# CC2640R2F_Bluetooth_Beacon.net
KiCad netlist of a schematic drawn in Altium Designer
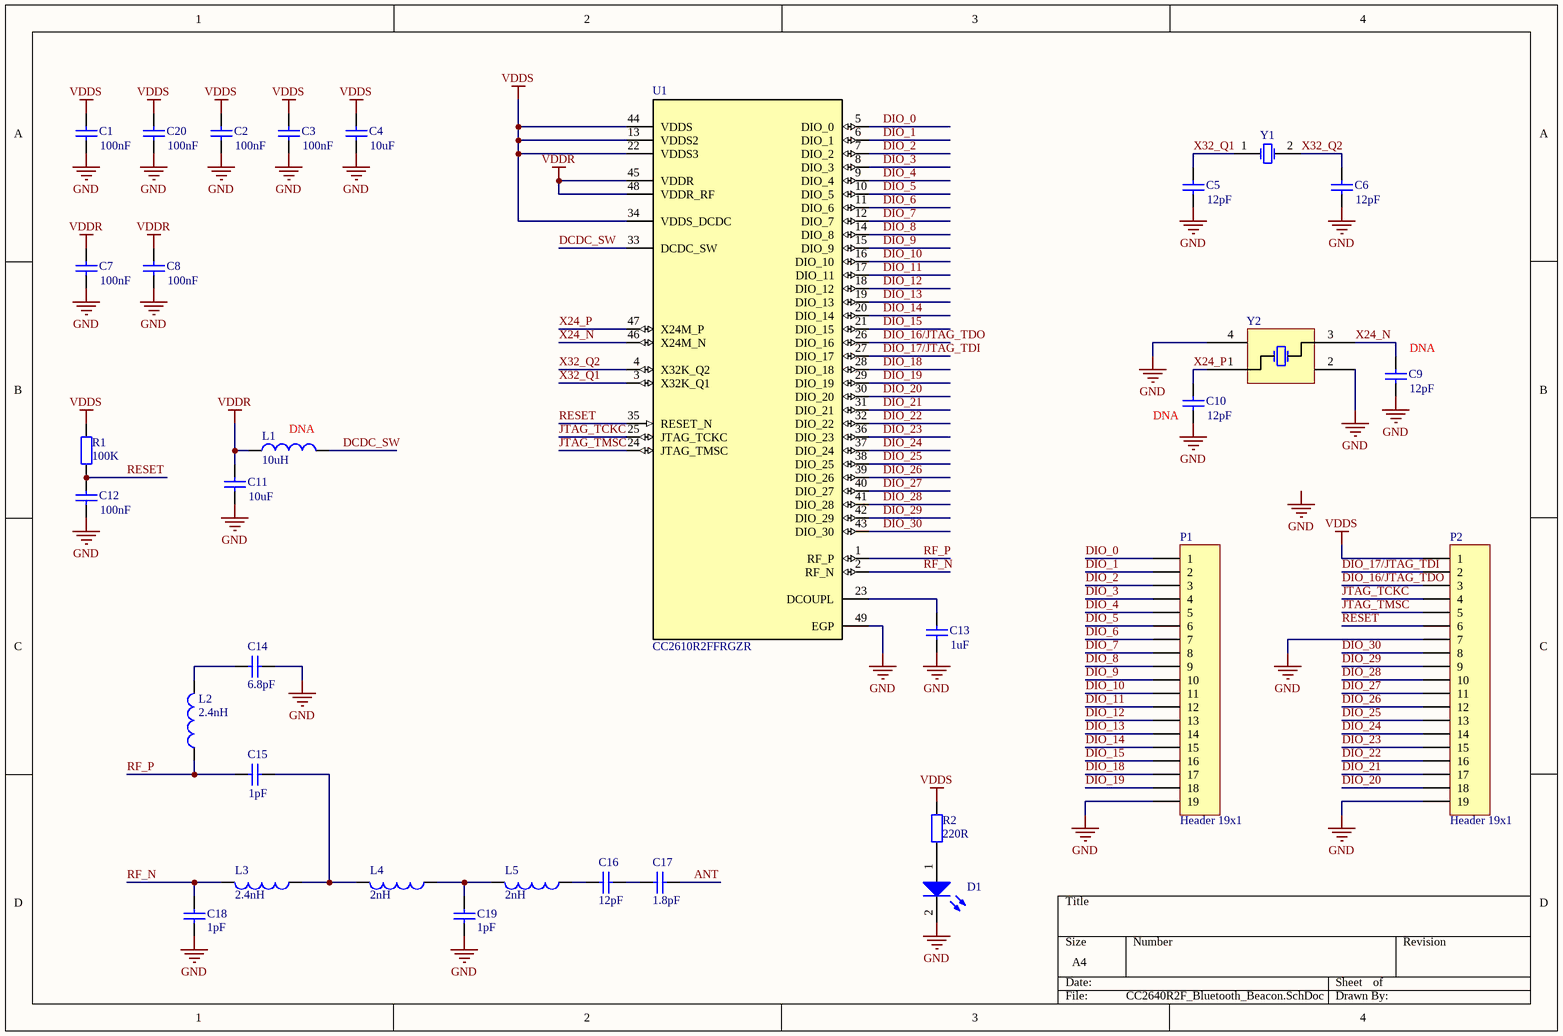
[diagram p0: CC2640R2F_Bluetooth_Beacon.SchDoc]

(export (version "E")
  (design (tool "Eeschema 10.0.6"))
  (components
    (comp (ref "C1")
      (value "100nF")
      (footprint "0603")
      (description "Capacitor")
      (fields (field (name "MPN") "885012206071") (field (name "MANUFACTURER") "Wurth Electronics"))
      (libsource (lib "LibraryTG") (part "Cap"))
    )
    (comp (ref "C2")
      (value "100nF")
      (footprint "0603")
      (description "Capacitor")
      (fields (field (name "MPN") "885012206071") (field (name "MANUFACTURER") "Wurth Electronics"))
      (libsource (lib "LibraryTG") (part "Cap"))
    )
    (comp (ref "C3")
      (value "100nF")
      (footprint "0603")
      (description "Capacitor")
      (fields (field (name "MPN") "885012206071") (field (name "MANUFACTURER") "Wurth Electronics"))
      (libsource (lib "LibraryTG") (part "Cap"))
    )
    (comp (ref "C4")
      (value "10uF")
      (footprint "0603")
      (description "Capacitor")
      (fields (field (name "MPN") "JMK107BJ106MA-T") (field (name "MANUFACTURER") "Taiyo Yuden"))
      (libsource (lib "LibraryTG") (part "Cap"))
    )
    (comp (ref "C5")
      (value "12pF")
      (footprint "0603")
      (description "Capacitor")
      (fields (field (name "MPN") "VJ0603A120KXJPW1BC") (field (name "MANUFACTURER") "Vishay / Vitramon"))
      (libsource (lib "LibraryTG") (part "Cap"))
    )
    (comp (ref "C6")
      (value "12pF")
      (footprint "0603")
      (description "Capacitor")
      (fields (field (name "MPN") "VJ0603A120KXJPW1BC") (field (name "MANUFACTURER") "Vishay / Vitramon"))
      (libsource (lib "LibraryTG") (part "Cap"))
    )
    (comp (ref "C7")
      (value "100nF")
      (footprint "0603")
      (description "Capacitor")
      (fields (field (name "MPN") "885012206071") (field (name "MANUFACTURER") "Wurth Electronics"))
      (libsource (lib "LibraryTG") (part "Cap"))
    )
    (comp (ref "C8")
      (value "100nF")
      (footprint "0603")
      (description "Capacitor")
      (fields (field (name "MPN") "885012206071") (field (name "MANUFACTURER") "Wurth Electronics"))
      (libsource (lib "LibraryTG") (part "Cap"))
    )
    (comp (ref "C9")
      (value "DNA")
      (footprint "0603")
      (description "Capacitor")
      (fields
        (field (name "ALTIUM_VALUE") "12pF")
        (field (name "MPN") "VJ0603A120KXJPW1BC")
        (field (name "MANUFACTURER") "Vishay / Vitramon")
      )
      (libsource (lib "LibraryTG") (part "Cap"))
    )
    (comp (ref "C10")
      (value "DNA")
      (footprint "0603")
      (description "Capacitor")
      (fields
        (field (name "ALTIUM_VALUE") "12pF")
        (field (name "MPN") "VJ0603A120KXJPW1BC")
        (field (name "MANUFACTURER") "Vishay / Vitramon")
      )
      (libsource (lib "LibraryTG") (part "Cap"))
    )
    (comp (ref "C11")
      (value "10uF")
      (footprint "0603")
      (description "Capacitor")
      (fields (field (name "MPN") "JMK107BJ106MA-T") (field (name "MANUFACTURER") "Taiyo Yuden"))
      (libsource (lib "LibraryTG") (part "Cap"))
    )
    (comp (ref "C12")
      (value "100nF")
      (footprint "0603")
      (description "Capacitor")
      (fields (field (name "MPN") "885012206071") (field (name "MANUFACTURER") "Wurth Electronics"))
      (libsource (lib "LibraryTG") (part "Cap"))
    )
    (comp (ref "C13")
      (value "1uF")
      (footprint "0603")
      (description "Capacitor")
      (fields (field (name "MPN") "885012106022") (field (name "MANUFACTURER") "Wurth Electronics"))
      (libsource (lib "LibraryTG") (part "Cap"))
    )
    (comp (ref "C14")
      (value "6.8pF")
      (footprint "0603")
      (description "Capacitor")
      (fields (field (name "MPN") "885012006031") (field (name "MANUFACTURER") "Wurth Electronics"))
      (libsource (lib "LibraryTG") (part "Cap"))
    )
    (comp (ref "C15")
      (value "1pF")
      (footprint "0603")
      (description "Capacitor")
      (fields (field (name "MPN") "885012006087") (field (name "MANUFACTURER") "Wurth Electronics"))
      (libsource (lib "LibraryTG") (part "Cap"))
    )
    (comp (ref "C16")
      (value "12pF")
      (footprint "0603")
      (description "Capacitor")
      (fields (field (name "MPN") "VJ0603A120KXJPW1BC") (field (name "MANUFACTURER") "Vishay / Vitramon"))
      (libsource (lib "LibraryTG") (part "Cap"))
    )
    (comp (ref "C17")
      (value "1.8pF")
      (footprint "0603")
      (description "Capacitor")
      (fields (field (name "MPN") "CC0603CRNPO9BN1R8") (field (name "MANUFACTURER") "Yageo"))
      (libsource (lib "LibraryTG") (part "Cap"))
    )
    (comp (ref "C18")
      (value "1pF")
      (footprint "0603")
      (description "Capacitor")
      (fields (field (name "MPN") "885012006087") (field (name "MANUFACTURER") "Wurth Electronics"))
      (libsource (lib "LibraryTG") (part "Cap"))
    )
    (comp (ref "C19")
      (value "1pF")
      (footprint "0603")
      (description "Capacitor")
      (fields (field (name "MPN") "885012006087") (field (name "MANUFACTURER") "Wurth Electronics"))
      (libsource (lib "LibraryTG") (part "Cap"))
    )
    (comp (ref "C20")
      (value "100nF")
      (footprint "0603")
      (description "Capacitor")
      (fields (field (name "MPN") "885012206071") (field (name "MANUFACTURER") "Wurth Electronics"))
      (libsource (lib "LibraryTG") (part "Cap"))
    )
    (comp (ref "D1")
      (value "LED")
      (footprint "0603")
      (description "Typical RED GaAs LED")
      (fields (field (name "MPN") "150060GS75000") (field (name "MANUFACTURER") "Wurth Electronics"))
      (libsource (lib "LibraryTG") (part "LED"))
    )
    (comp (ref "L1")
      (value "DNA")
      (footprint "0603")
      (description "Inductor")
      (fields (field (name "ALTIUM_VALUE") "10uH") (field (name "MPN") "MLZ1608E100MT"))
      (libsource (lib "LibraryTG") (part "Inductor"))
    )
    (comp (ref "L2")
      (value "2.4nH")
      (footprint "0603")
      (description "Inductor")
      (fields (field (name "MPN") "LQW18AN2N4C80D") (field (name "MANUFACTURER") "Murata Electronics"))
      (libsource (lib "LibraryTG") (part "Inductor"))
    )
    (comp (ref "L3")
      (value "2.4nH")
      (footprint "0603")
      (description "Inductor")
      (fields (field (name "MPN") "LQW18AN2N4C80D") (field (name "MANUFACTURER") "Murata Electronics"))
      (libsource (lib "LibraryTG") (part "Inductor"))
    )
    (comp (ref "L4")
      (value "2nH")
      (footprint "0603")
      (description "Inductor")
      (fields (field (name "MPN") "LQG15HZ2N0S02D") (field (name "MANUFACTURER") "Murata Electronics"))
      (libsource (lib "LibraryTG") (part "Inductor"))
    )
    (comp (ref "L5")
      (value "2nH")
      (footprint "0603")
      (description "Inductor")
      (fields (field (name "MPN") "LQG15HZ2N0S02D") (field (name "MANUFACTURER") "Murata Electronics"))
      (libsource (lib "LibraryTG") (part "Inductor"))
    )
    (comp (ref "P1")
      (value "Header 19x1")
      (footprint "HDR1X19")
      (description "Header, 19-Pin")
      (libsource (lib "LibraryTG") (part "Header 19x1"))
    )
    (comp (ref "P2")
      (value "Header 19x1")
      (footprint "HDR1X19")
      (description "Header, 19-Pin")
      (libsource (lib "LibraryTG") (part "Header 19x1"))
    )
    (comp (ref "R1")
      (value "100K")
      (footprint "0603")
      (description "Resistor")
      (fields (field (name "MPN") "ESR03EZPJ104") (field (name "MANUFACTURER") "ROHM Semiconductor"))
      (libsource (lib "LibraryTG") (part "Res"))
    )
    (comp (ref "R2")
      (value "220R")
      (footprint "0603")
      (description "Resistor")
      (fields (field (name "MPN") "ESR03EZPJ221") (field (name "MANUFACTURER") "ROHM Semiconductor"))
      (libsource (lib "LibraryTG") (part "Res"))
    )
    (comp (ref "U1")
      (value "CC2610R2FFRGZR")
      (footprint "VQFN-48")
      (description "CC2640R2F SimpleLink™ Bluetooth® low energy Wireless MCU")
      (fields (field (name "MPN") "CC2640R2FRGZR") (field (name "MANUFACTURER") "Texas Instruments"))
      (libsource (lib "LibraryTG") (part "CC2640R2FRGZR"))
    )
    (comp (ref "Y1")
      (value "XTAL")
      (footprint "FC-135")
      (description "Crystal Oscillator")
      (fields (field (name "MPN") "FC-135 32.7680KA-AG3") (field (name "MANUFACTURER") "Epson Timing"))
      (libsource (lib "LibraryTG") (part "XTAL"))
    )
    (comp (ref "Y2")
      (value "XTAL-2")
      (footprint "TX-3225")
      (description "Crystal Oscillator")
      (fields (field (name "MPN") "TSX-3225 24.0000MF15X-AC3") (field (name "MANUFACTURER") "Epson Timing"))
      (libsource (lib "LibraryTG") (part "XTAL-2"))
    )
  )
  (nets
    (net (code "1") (name "/ANT") (class "Default")
      (node (ref "C17") (pin "1") (pinfunction "1_1") (pintype "passive"))
    )
    (net (code "2") (name "/DCDC_SW") (class "Default")
      (node (ref "L1") (pin "2") (pinfunction "2_2") (pintype "passive"))
      (node (ref "U1") (pin "33") (pinfunction "DCDC_SW_33") (pintype "power_in"))
    )
    (net (code "3") (name "/DIO_0") (class "Default")
      (node (ref "P1") (pin "1") (pinfunction "1_1") (pintype "passive"))
      (node (ref "U1") (pin "5") (pinfunction "DIO_0_5") (pintype "bidirectional"))
    )
    (net (code "4") (name "/DIO_1") (class "Default")
      (node (ref "P1") (pin "2") (pinfunction "2_2") (pintype "passive"))
      (node (ref "U1") (pin "6") (pinfunction "DIO_1_6") (pintype "bidirectional"))
    )
    (net (code "5") (name "/DIO_2") (class "Default")
      (node (ref "P1") (pin "3") (pinfunction "3_3") (pintype "passive"))
      (node (ref "U1") (pin "7") (pinfunction "DIO_2_7") (pintype "bidirectional"))
    )
    (net (code "6") (name "/DIO_3") (class "Default")
      (node (ref "P1") (pin "4") (pinfunction "4_4") (pintype "passive"))
      (node (ref "U1") (pin "8") (pinfunction "DIO_3_8") (pintype "bidirectional"))
    )
    (net (code "7") (name "/DIO_4") (class "Default")
      (node (ref "P1") (pin "5") (pinfunction "5_5") (pintype "passive"))
      (node (ref "U1") (pin "9") (pinfunction "DIO_4_9") (pintype "bidirectional"))
    )
    (net (code "8") (name "/DIO_5") (class "Default")
      (node (ref "P1") (pin "6") (pinfunction "6_6") (pintype "passive"))
      (node (ref "U1") (pin "10") (pinfunction "DIO_5_10") (pintype "bidirectional"))
    )
    (net (code "9") (name "/DIO_6") (class "Default")
      (node (ref "P1") (pin "7") (pinfunction "7_7") (pintype "passive"))
      (node (ref "U1") (pin "11") (pinfunction "DIO_6_11") (pintype "bidirectional"))
    )
    (net (code "10") (name "/DIO_7") (class "Default")
      (node (ref "P1") (pin "8") (pinfunction "8_8") (pintype "passive"))
      (node (ref "U1") (pin "12") (pinfunction "DIO_7_12") (pintype "bidirectional"))
    )
    (net (code "11") (name "/DIO_8") (class "Default")
      (node (ref "P1") (pin "9") (pinfunction "9_9") (pintype "passive"))
      (node (ref "U1") (pin "14") (pinfunction "DIO_8_14") (pintype "bidirectional"))
    )
    (net (code "12") (name "/DIO_9") (class "Default")
      (node (ref "P1") (pin "10") (pinfunction "10_10") (pintype "passive"))
      (node (ref "U1") (pin "15") (pinfunction "DIO_9_15") (pintype "bidirectional"))
    )
    (net (code "13") (name "/DIO_10") (class "Default")
      (node (ref "P1") (pin "11") (pinfunction "11_11") (pintype "passive"))
      (node (ref "U1") (pin "16") (pinfunction "DIO_10_16") (pintype "bidirectional"))
    )
    (net (code "14") (name "/DIO_11") (class "Default")
      (node (ref "P1") (pin "12") (pinfunction "12_12") (pintype "passive"))
      (node (ref "U1") (pin "17") (pinfunction "DIO_11_17") (pintype "bidirectional"))
    )
    (net (code "15") (name "/DIO_12") (class "Default")
      (node (ref "P1") (pin "13") (pinfunction "13_13") (pintype "passive"))
      (node (ref "U1") (pin "18") (pinfunction "DIO_12_18") (pintype "bidirectional"))
    )
    (net (code "16") (name "/DIO_13") (class "Default")
      (node (ref "P1") (pin "14") (pinfunction "14_14") (pintype "passive"))
      (node (ref "U1") (pin "19") (pinfunction "DIO_13_19") (pintype "bidirectional"))
    )
    (net (code "17") (name "/DIO_14") (class "Default")
      (node (ref "P1") (pin "15") (pinfunction "15_15") (pintype "passive"))
      (node (ref "U1") (pin "20") (pinfunction "DIO_14_20") (pintype "bidirectional"))
    )
    (net (code "18") (name "/DIO_15") (class "Default")
      (node (ref "P1") (pin "16") (pinfunction "16_16") (pintype "passive"))
      (node (ref "U1") (pin "21") (pinfunction "DIO_15_21") (pintype "bidirectional"))
    )
    (net (code "19") (name "/DIO_16{slash}JTAG_TDO") (class "Default")
      (node (ref "P2") (pin "3") (pinfunction "3_3") (pintype "passive"))
      (node (ref "U1") (pin "26") (pinfunction "DIO_16_26") (pintype "bidirectional"))
    )
    (net (code "20") (name "/DIO_17{slash}JTAG_TDI") (class "Default")
      (node (ref "P2") (pin "2") (pinfunction "2_2") (pintype "passive"))
      (node (ref "U1") (pin "27") (pinfunction "DIO_17_27") (pintype "bidirectional"))
    )
    (net (code "21") (name "/DIO_18") (class "Default")
      (node (ref "P1") (pin "17") (pinfunction "17_17") (pintype "passive"))
      (node (ref "U1") (pin "28") (pinfunction "DIO_18_28") (pintype "bidirectional"))
    )
    (net (code "22") (name "/DIO_19") (class "Default")
      (node (ref "P1") (pin "18") (pinfunction "18_18") (pintype "passive"))
      (node (ref "U1") (pin "29") (pinfunction "DIO_19_29") (pintype "bidirectional"))
    )
    (net (code "23") (name "/DIO_20") (class "Default")
      (node (ref "P2") (pin "18") (pinfunction "18_18") (pintype "passive"))
      (node (ref "U1") (pin "30") (pinfunction "DIO_20_30") (pintype "bidirectional"))
    )
    (net (code "24") (name "/DIO_21") (class "Default")
      (node (ref "P2") (pin "17") (pinfunction "17_17") (pintype "passive"))
      (node (ref "U1") (pin "31") (pinfunction "DIO_21_31") (pintype "bidirectional"))
    )
    (net (code "25") (name "/DIO_22") (class "Default")
      (node (ref "P2") (pin "16") (pinfunction "16_16") (pintype "passive"))
      (node (ref "U1") (pin "32") (pinfunction "DIO_22_32") (pintype "bidirectional"))
    )
    (net (code "26") (name "/DIO_23") (class "Default")
      (node (ref "P2") (pin "15") (pinfunction "15_15") (pintype "passive"))
      (node (ref "U1") (pin "36") (pinfunction "DIO_23_36") (pintype "bidirectional"))
    )
    (net (code "27") (name "/DIO_24") (class "Default")
      (node (ref "P2") (pin "14") (pinfunction "14_14") (pintype "passive"))
      (node (ref "U1") (pin "37") (pinfunction "DIO_24_37") (pintype "bidirectional"))
    )
    (net (code "28") (name "/DIO_25") (class "Default")
      (node (ref "P2") (pin "13") (pinfunction "13_13") (pintype "passive"))
      (node (ref "U1") (pin "38") (pinfunction "DIO_25_38") (pintype "bidirectional"))
    )
    (net (code "29") (name "/DIO_26") (class "Default")
      (node (ref "P2") (pin "12") (pinfunction "12_12") (pintype "passive"))
      (node (ref "U1") (pin "39") (pinfunction "DIO_26_39") (pintype "bidirectional"))
    )
    (net (code "30") (name "/DIO_27") (class "Default")
      (node (ref "P2") (pin "11") (pinfunction "11_11") (pintype "passive"))
      (node (ref "U1") (pin "40") (pinfunction "DIO_27_40") (pintype "bidirectional"))
    )
    (net (code "31") (name "/DIO_28") (class "Default")
      (node (ref "P2") (pin "10") (pinfunction "10_10") (pintype "passive"))
      (node (ref "U1") (pin "41") (pinfunction "DIO_28_41") (pintype "bidirectional"))
    )
    (net (code "32") (name "/DIO_29") (class "Default")
      (node (ref "P2") (pin "9") (pinfunction "9_9") (pintype "passive"))
      (node (ref "U1") (pin "42") (pinfunction "DIO_29_42") (pintype "bidirectional"))
    )
    (net (code "33") (name "/DIO_30") (class "Default")
      (node (ref "P2") (pin "8") (pinfunction "8_8") (pintype "passive"))
      (node (ref "U1") (pin "43") (pinfunction "DIO_30_43") (pintype "bidirectional"))
    )
    (net (code "34") (name "/JTAG_TCKC") (class "Default")
      (node (ref "P2") (pin "4") (pinfunction "4_4") (pintype "passive"))
      (node (ref "U1") (pin "25") (pinfunction "JTAG_TCKC_25") (pintype "bidirectional"))
    )
    (net (code "35") (name "/JTAG_TMSC") (class "Default")
      (node (ref "P2") (pin "5") (pinfunction "5_5") (pintype "passive"))
      (node (ref "U1") (pin "24") (pinfunction "JTAG_TMSC_24") (pintype "bidirectional"))
    )
    (net (code "36") (name "/RESET") (class "Default")
      (node (ref "C12") (pin "2") (pinfunction "2_2") (pintype "passive"))
      (node (ref "P2") (pin "6") (pinfunction "6_6") (pintype "passive"))
      (node (ref "R1") (pin "1") (pinfunction "1_1") (pintype "passive"))
      (node (ref "U1") (pin "35") (pinfunction "RESET_N_35") (pintype "input"))
    )
    (net (code "37") (name "/RF_N") (class "Default")
      (node (ref "C18") (pin "2") (pinfunction "2_2") (pintype "passive"))
      (node (ref "L3") (pin "2") (pinfunction "2_2") (pintype "passive"))
      (node (ref "U1") (pin "2") (pinfunction "RF_N_2") (pintype "bidirectional"))
    )
    (net (code "38") (name "/RF_P") (class "Default")
      (node (ref "C15") (pin "2") (pinfunction "2_2") (pintype "passive"))
      (node (ref "L2") (pin "1") (pinfunction "1_1") (pintype "passive"))
      (node (ref "U1") (pin "1") (pinfunction "RF_P_1") (pintype "bidirectional"))
    )
    (net (code "39") (name "/X24_N") (class "Default")
      (node (ref "C9") (pin "2") (pinfunction "2_2") (pintype "passive"))
      (node (ref "U1") (pin "46") (pinfunction "X24M_N_46") (pintype "bidirectional"))
      (node (ref "Y2") (pin "3") (pinfunction "3_3") (pintype "passive"))
    )
    (net (code "40") (name "/X24_P") (class "Default")
      (node (ref "C10") (pin "2") (pinfunction "2_2") (pintype "passive"))
      (node (ref "U1") (pin "47") (pinfunction "X24M_P_47") (pintype "bidirectional"))
      (node (ref "Y2") (pin "1") (pinfunction "1_1") (pintype "passive"))
    )
    (net (code "41") (name "/X32_Q1") (class "Default")
      (node (ref "C5") (pin "2") (pinfunction "2_2") (pintype "passive"))
      (node (ref "U1") (pin "3") (pinfunction "X32K_Q1_3") (pintype "bidirectional"))
      (node (ref "Y1") (pin "1") (pinfunction "OSC1_1") (pintype "passive"))
    )
    (net (code "42") (name "/X32_Q2") (class "Default")
      (node (ref "C6") (pin "2") (pinfunction "2_2") (pintype "passive"))
      (node (ref "U1") (pin "4") (pinfunction "X32K_Q2_4") (pintype "bidirectional"))
      (node (ref "Y1") (pin "2") (pinfunction "OSC2_2") (pintype "passive"))
    )
    (net (code "43") (name "GND") (class "Default")
      (node (ref "C1") (pin "1") (pinfunction "1_1") (pintype "passive"))
      (node (ref "C10") (pin "1") (pinfunction "1_1") (pintype "passive"))
      (node (ref "C11") (pin "1") (pinfunction "1_1") (pintype "passive"))
      (node (ref "C12") (pin "1") (pinfunction "1_1") (pintype "passive"))
      (node (ref "C13") (pin "1") (pinfunction "1_1") (pintype "passive"))
      (node (ref "C14") (pin "1") (pinfunction "1_1") (pintype "passive"))
      (node (ref "C18") (pin "1") (pinfunction "1_1") (pintype "passive"))
      (node (ref "C19") (pin "1") (pinfunction "1_1") (pintype "passive"))
      (node (ref "C2") (pin "1") (pinfunction "1_1") (pintype "passive"))
      (node (ref "C20") (pin "1") (pinfunction "1_1") (pintype "passive"))
      (node (ref "C3") (pin "1") (pinfunction "1_1") (pintype "passive"))
      (node (ref "C4") (pin "1") (pinfunction "1_1") (pintype "passive"))
      (node (ref "C5") (pin "1") (pinfunction "1_1") (pintype "passive"))
      (node (ref "C6") (pin "1") (pinfunction "1_1") (pintype "passive"))
      (node (ref "C7") (pin "1") (pinfunction "1_1") (pintype "passive"))
      (node (ref "C8") (pin "1") (pinfunction "1_1") (pintype "passive"))
      (node (ref "C9") (pin "1") (pinfunction "1_1") (pintype "passive"))
      (node (ref "D1") (pin "2") (pinfunction "K_2") (pintype "passive"))
      (node (ref "P1") (pin "19") (pinfunction "19_19") (pintype "passive"))
      (node (ref "P2") (pin "19") (pinfunction "19_19") (pintype "passive"))
      (node (ref "P2") (pin "7") (pinfunction "7_7") (pintype "passive"))
      (node (ref "U1") (pin "49") (pinfunction "EGP_49") (pintype "power_in"))
      (node (ref "Y2") (pin "2") (pinfunction "2_2") (pintype "passive"))
      (node (ref "Y2") (pin "4") (pinfunction "4_4") (pintype "passive"))
    )
    (net (code "44") (name "Net-(C14-Pad2)") (class "Default")
      (node (ref "C14") (pin "2") (pinfunction "2_2") (pintype "passive"))
      (node (ref "L2") (pin "2") (pinfunction "2_2") (pintype "passive"))
    )
    (net (code "45") (name "Net-(C15-Pad1)") (class "Default")
      (node (ref "C15") (pin "1") (pinfunction "1_1") (pintype "passive"))
      (node (ref "L3") (pin "1") (pinfunction "1_1") (pintype "passive"))
      (node (ref "L4") (pin "2") (pinfunction "2_2") (pintype "passive"))
    )
    (net (code "46") (name "Net-(C16-Pad1)") (class "Default")
      (node (ref "C16") (pin "1") (pinfunction "1_1") (pintype "passive"))
      (node (ref "C17") (pin "2") (pinfunction "2_2") (pintype "passive"))
    )
    (net (code "47") (name "Net-(C16-Pad2)") (class "Default")
      (node (ref "C16") (pin "2") (pinfunction "2_2") (pintype "passive"))
      (node (ref "L5") (pin "1") (pinfunction "1_1") (pintype "passive"))
    )
    (net (code "48") (name "Net-(C19-Pad2)") (class "Default")
      (node (ref "C19") (pin "2") (pinfunction "2_2") (pintype "passive"))
      (node (ref "L4") (pin "1") (pinfunction "1_1") (pintype "passive"))
      (node (ref "L5") (pin "2") (pinfunction "2_2") (pintype "passive"))
    )
    (net (code "49") (name "Net-(D1-A)") (class "Default")
      (node (ref "D1") (pin "1") (pinfunction "A_1") (pintype "passive"))
      (node (ref "R2") (pin "1") (pinfunction "1_1") (pintype "passive"))
    )
    (net (code "50") (name "Net-(U1-DCOUPL)") (class "Default")
      (node (ref "C13") (pin "2") (pinfunction "2_2") (pintype "passive"))
      (node (ref "U1") (pin "23") (pinfunction "DCOUPL_23") (pintype "power_in"))
    )
    (net (code "51") (name "VDDR") (class "Default")
      (node (ref "C11") (pin "2") (pinfunction "2_2") (pintype "passive"))
      (node (ref "C7") (pin "2") (pinfunction "2_2") (pintype "passive"))
      (node (ref "C8") (pin "2") (pinfunction "2_2") (pintype "passive"))
      (node (ref "L1") (pin "1") (pinfunction "1_1") (pintype "passive"))
      (node (ref "U1") (pin "45") (pinfunction "VDDR_45") (pintype "power_in"))
      (node (ref "U1") (pin "48") (pinfunction "VDDR_RF_48") (pintype "power_in"))
    )
    (net (code "52") (name "VDDS") (class "Default")
      (node (ref "C1") (pin "2") (pinfunction "2_2") (pintype "passive"))
      (node (ref "C2") (pin "2") (pinfunction "2_2") (pintype "passive"))
      (node (ref "C20") (pin "2") (pinfunction "2_2") (pintype "passive"))
      (node (ref "C3") (pin "2") (pinfunction "2_2") (pintype "passive"))
      (node (ref "C4") (pin "2") (pinfunction "2_2") (pintype "passive"))
      (node (ref "P2") (pin "1") (pinfunction "1_1") (pintype "passive"))
      (node (ref "R1") (pin "2") (pinfunction "2_2") (pintype "passive"))
      (node (ref "R2") (pin "2") (pinfunction "2_2") (pintype "passive"))
      (node (ref "U1") (pin "13") (pinfunction "VDDS2_13") (pintype "power_in"))
      (node (ref "U1") (pin "22") (pinfunction "VDDS3_22") (pintype "power_in"))
      (node (ref "U1") (pin "34") (pinfunction "VDDS_DCDC_34") (pintype "power_in"))
      (node (ref "U1") (pin "44") (pinfunction "VDDS_44") (pintype "power_in"))
    )
  )
)
